# USB_Switch_PCB.net
KiCad netlist of a schematic drawn in EAGLE
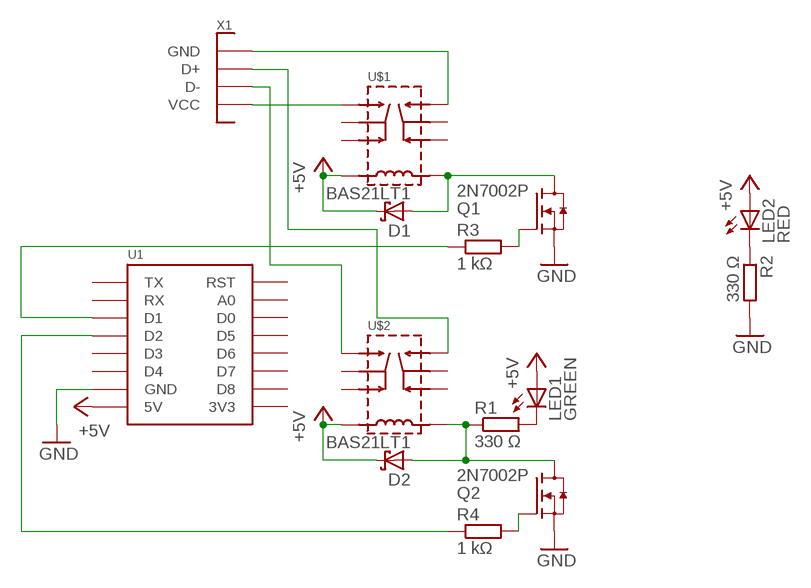
[diagram p0: schematic, sheet 1]

(export (version "E")
  (design (tool "Eeschema 10.0.6"))
  (components
    (comp (ref "D1")
      (value "BAS21LT1")
      (footprint "eagle-import:SOT23")
      (libsource (lib "eagle-import") (part "BAS40"))
    )
    (comp (ref "D2")
      (value "BAS21LT1")
      (footprint "eagle-import:SOT23")
      (libsource (lib "eagle-import") (part "BAS40"))
    )
    (comp (ref "LED1")
      (value "GREEN")
      (footprint "eagle-import:CHIPLED_0805")
      (libsource (lib "eagle-import") (part "LEDCHIPLED_0805"))
    )
    (comp (ref "LED2")
      (value "RED")
      (footprint "eagle-import:CHIPLED_0805")
      (libsource (lib "eagle-import") (part "LEDCHIPLED_0805"))
    )
    (comp (ref "Q1")
      (value "2N7002P")
      (footprint "eagle-import:SOT23")
      (libsource (lib "eagle-import") (part "2N7002P2N7002P"))
    )
    (comp (ref "Q2")
      (value "2N7002P")
      (footprint "eagle-import:SOT23")
      (libsource (lib "eagle-import") (part "2N7002P2N7002P"))
    )
    (comp (ref "R1")
      (value "330 Ω")
      (footprint "eagle-import:R0603")
      (libsource (lib "eagle-import") (part "R-EU_R0603"))
    )
    (comp (ref "R2")
      (value "330 Ω")
      (footprint "eagle-import:R0603")
      (libsource (lib "eagle-import") (part "R-EU_R0603"))
    )
    (comp (ref "R3")
      (value "1 kΩ")
      (footprint "eagle-import:R0603")
      (libsource (lib "eagle-import") (part "R-EU_R0603"))
    )
    (comp (ref "R4")
      (value "1 kΩ")
      (footprint "eagle-import:R0603")
      (libsource (lib "eagle-import") (part "R-EU_R0603"))
    )
    (comp (ref "U$1")
      (value "EC2-5NUEC2-5NU")
      (footprint "eagle-import:EC2-5NU")
      (libsource (lib "eagle-import") (part "EC2-5NUEC2-5NU"))
    )
    (comp (ref "U$2")
      (value "EC2-5NUEC2-5NU")
      (footprint "eagle-import:EC2-5NU")
      (libsource (lib "eagle-import") (part "EC2-5NUEC2-5NU"))
    )
    (comp (ref "U1")
      (value "D1MINI")
      (footprint "eagle-import:D1MINI")
      (libsource (lib "eagle-import") (part "D1MINI"))
    )
    (comp (ref "X1")
      (value "UE27-USBA")
      (footprint "eagle-import:UE27-USBA")
      (libsource (lib "eagle-import") (part "UE27-USBA"))
    )
  )
  (nets
    (net (code "1") (name "+5V") (class "Default")
      (node (ref "D1") (pin "3") (pinfunction "C_3") (pintype "passive"))
      (node (ref "D2") (pin "3") (pinfunction "C_3") (pintype "passive"))
      (node (ref "LED1") (pin "A") (pinfunction "A_A") (pintype "passive"))
      (node (ref "LED2") (pin "A") (pinfunction "A_A") (pintype "passive"))
      (node (ref "U$1") (pin "1") (pinfunction "P_1") (pintype "bidirectional"))
      (node (ref "U$2") (pin "1") (pinfunction "P_1") (pintype "bidirectional"))
      (node (ref "U1") (pin "5V") (pinfunction "5V_5V") (pintype "bidirectional"))
    )
    (net (code "2") (name "GND") (class "Default")
      (node (ref "Q1") (pin "2") (pinfunction "S_2") (pintype "passive"))
      (node (ref "Q2") (pin "2") (pinfunction "S_2") (pintype "passive"))
      (node (ref "R2") (pin "2") (pinfunction "2_2") (pintype "passive"))
      (node (ref "U1") (pin "GND") (pinfunction "GND_GND") (pintype "bidirectional"))
    )
    (net (code "3") (name "Net-(D1-A)") (class "Default")
      (node (ref "D1") (pin "1") (pinfunction "A_1") (pintype "passive"))
      (node (ref "Q1") (pin "3") (pinfunction "D_3") (pintype "passive"))
      (node (ref "U$1") (pin "12") (pinfunction "N_12") (pintype "bidirectional"))
    )
    (net (code "4") (name "Net-(D2-A)") (class "Default")
      (node (ref "D2") (pin "1") (pinfunction "A_1") (pintype "passive"))
      (node (ref "Q2") (pin "3") (pinfunction "D_3") (pintype "passive"))
      (node (ref "R1") (pin "1") (pinfunction "1_1") (pintype "passive"))
      (node (ref "U$2") (pin "12") (pinfunction "N_12") (pintype "bidirectional"))
    )
    (net (code "5") (name "Net-(LED1-PadC)") (class "Default")
      (node (ref "LED1") (pin "C") (pinfunction "C_C") (pintype "passive"))
      (node (ref "R1") (pin "2") (pinfunction "2_2") (pintype "passive"))
    )
    (net (code "6") (name "Net-(LED2-PadC)") (class "Default")
      (node (ref "LED2") (pin "C") (pinfunction "C_C") (pintype "passive"))
      (node (ref "R2") (pin "1") (pinfunction "1_1") (pintype "passive"))
    )
    (net (code "7") (name "Net-(Q1-G)") (class "Default")
      (node (ref "Q1") (pin "1") (pinfunction "G_1") (pintype "passive"))
      (node (ref "R3") (pin "2") (pinfunction "2_2") (pintype "passive"))
    )
    (net (code "8") (name "Net-(Q2-G)") (class "Default")
      (node (ref "Q2") (pin "1") (pinfunction "G_1") (pintype "passive"))
      (node (ref "R4") (pin "2") (pinfunction "2_2") (pintype "passive"))
    )
    (net (code "9") (name "Net-(R3-Pad1)") (class "Default")
      (node (ref "R3") (pin "1") (pinfunction "1_1") (pintype "passive"))
      (node (ref "U1") (pin "D1") (pinfunction "D1_D1") (pintype "bidirectional"))
    )
    (net (code "10") (name "Net-(R4-Pad1)") (class "Default")
      (node (ref "R4") (pin "1") (pinfunction "1_1") (pintype "passive"))
      (node (ref "U1") (pin "D2") (pinfunction "D2_D2") (pintype "bidirectional"))
    )
    (net (code "11") (name "Net-(U$1-A1)") (class "Default")
      (node (ref "U$1") (pin "5") (pinfunction "A1_5") (pintype "bidirectional"))
      (node (ref "X1") (pin "VCC") (pinfunction "VCC_VCC") (pintype "bidirectional"))
    )
    (net (code "12") (name "Net-(U$1-A2)") (class "Default")
      (node (ref "U$1") (pin "8") (pinfunction "A2_8") (pintype "bidirectional"))
      (node (ref "X1") (pin "GND") (pinfunction "GND_GND") (pintype "bidirectional"))
    )
    (net (code "13") (name "Net-(U$2-A1)") (class "Default")
      (node (ref "U$2") (pin "5") (pinfunction "A1_5") (pintype "bidirectional"))
      (node (ref "X1") (pin "D-") (pinfunction "D-_D-") (pintype "bidirectional"))
    )
    (net (code "14") (name "Net-(U$2-A2)") (class "Default")
      (node (ref "U$2") (pin "8") (pinfunction "A2_8") (pintype "bidirectional"))
      (node (ref "X1") (pin "D+") (pinfunction "D+_D+") (pintype "bidirectional"))
    )
    (net (code "15") (name "unconnected-(U$1-B1-Pad3)") (class "Default")
      (node (ref "U$1") (pin "3") (pinfunction "B1_3") (pintype "bidirectional"))
    )
    (net (code "16") (name "unconnected-(U$1-B2-Pad10)") (class "Default")
      (node (ref "U$1") (pin "10") (pinfunction "B2_10") (pintype "bidirectional"))
    )
    (net (code "17") (name "unconnected-(U$1-C1-Pad4)") (class "Default")
      (node (ref "U$1") (pin "4") (pinfunction "C1_4") (pintype "bidirectional"))
    )
    (net (code "18") (name "unconnected-(U$1-C2-Pad9)") (class "Default")
      (node (ref "U$1") (pin "9") (pinfunction "C2_9") (pintype "bidirectional"))
    )
    (net (code "19") (name "unconnected-(U$2-B1-Pad3)") (class "Default")
      (node (ref "U$2") (pin "3") (pinfunction "B1_3") (pintype "bidirectional"))
    )
    (net (code "20") (name "unconnected-(U$2-B2-Pad10)") (class "Default")
      (node (ref "U$2") (pin "10") (pinfunction "B2_10") (pintype "bidirectional"))
    )
    (net (code "21") (name "unconnected-(U$2-C1-Pad4)") (class "Default")
      (node (ref "U$2") (pin "4") (pinfunction "C1_4") (pintype "bidirectional"))
    )
    (net (code "22") (name "unconnected-(U$2-C2-Pad9)") (class "Default")
      (node (ref "U$2") (pin "9") (pinfunction "C2_9") (pintype "bidirectional"))
    )
    (net (code "23") (name "unconnected-(U1-Pad3V3)") (class "Default")
      (node (ref "U1") (pin "3V3") (pinfunction "3V3_3V3") (pintype "bidirectional"))
    )
    (net (code "24") (name "unconnected-(U1-PadA0)") (class "Default")
      (node (ref "U1") (pin "A0") (pinfunction "A0_A0") (pintype "bidirectional"))
    )
    (net (code "25") (name "unconnected-(U1-PadD0)") (class "Default")
      (node (ref "U1") (pin "D0") (pinfunction "D0_D0") (pintype "bidirectional"))
    )
    (net (code "26") (name "unconnected-(U1-PadD3)") (class "Default")
      (node (ref "U1") (pin "D3") (pinfunction "D3_D3") (pintype "bidirectional"))
    )
    (net (code "27") (name "unconnected-(U1-PadD4)") (class "Default")
      (node (ref "U1") (pin "D4") (pinfunction "D4_D4") (pintype "bidirectional"))
    )
    (net (code "28") (name "unconnected-(U1-PadD5)") (class "Default")
      (node (ref "U1") (pin "D5") (pinfunction "D5_D5") (pintype "bidirectional"))
    )
    (net (code "29") (name "unconnected-(U1-PadD6)") (class "Default")
      (node (ref "U1") (pin "D6") (pinfunction "D6_D6") (pintype "bidirectional"))
    )
    (net (code "30") (name "unconnected-(U1-PadD7)") (class "Default")
      (node (ref "U1") (pin "D7") (pinfunction "D7_D7") (pintype "bidirectional"))
    )
    (net (code "31") (name "unconnected-(U1-PadD8)") (class "Default")
      (node (ref "U1") (pin "D8") (pinfunction "D8_D8") (pintype "bidirectional"))
    )
    (net (code "32") (name "unconnected-(U1-PadRST)") (class "Default")
      (node (ref "U1") (pin "RST") (pinfunction "RST_RST") (pintype "bidirectional"))
    )
    (net (code "33") (name "unconnected-(U1-PadRX)") (class "Default")
      (node (ref "U1") (pin "RX") (pinfunction "RX_RX") (pintype "bidirectional"))
    )
    (net (code "34") (name "unconnected-(U1-PadTX)") (class "Default")
      (node (ref "U1") (pin "TX") (pinfunction "TX_TX") (pintype "bidirectional"))
    )
  )
)
